# SCH_card1_2024-03-21.net
KiCad netlist of a schematic drawn in EasyEDA
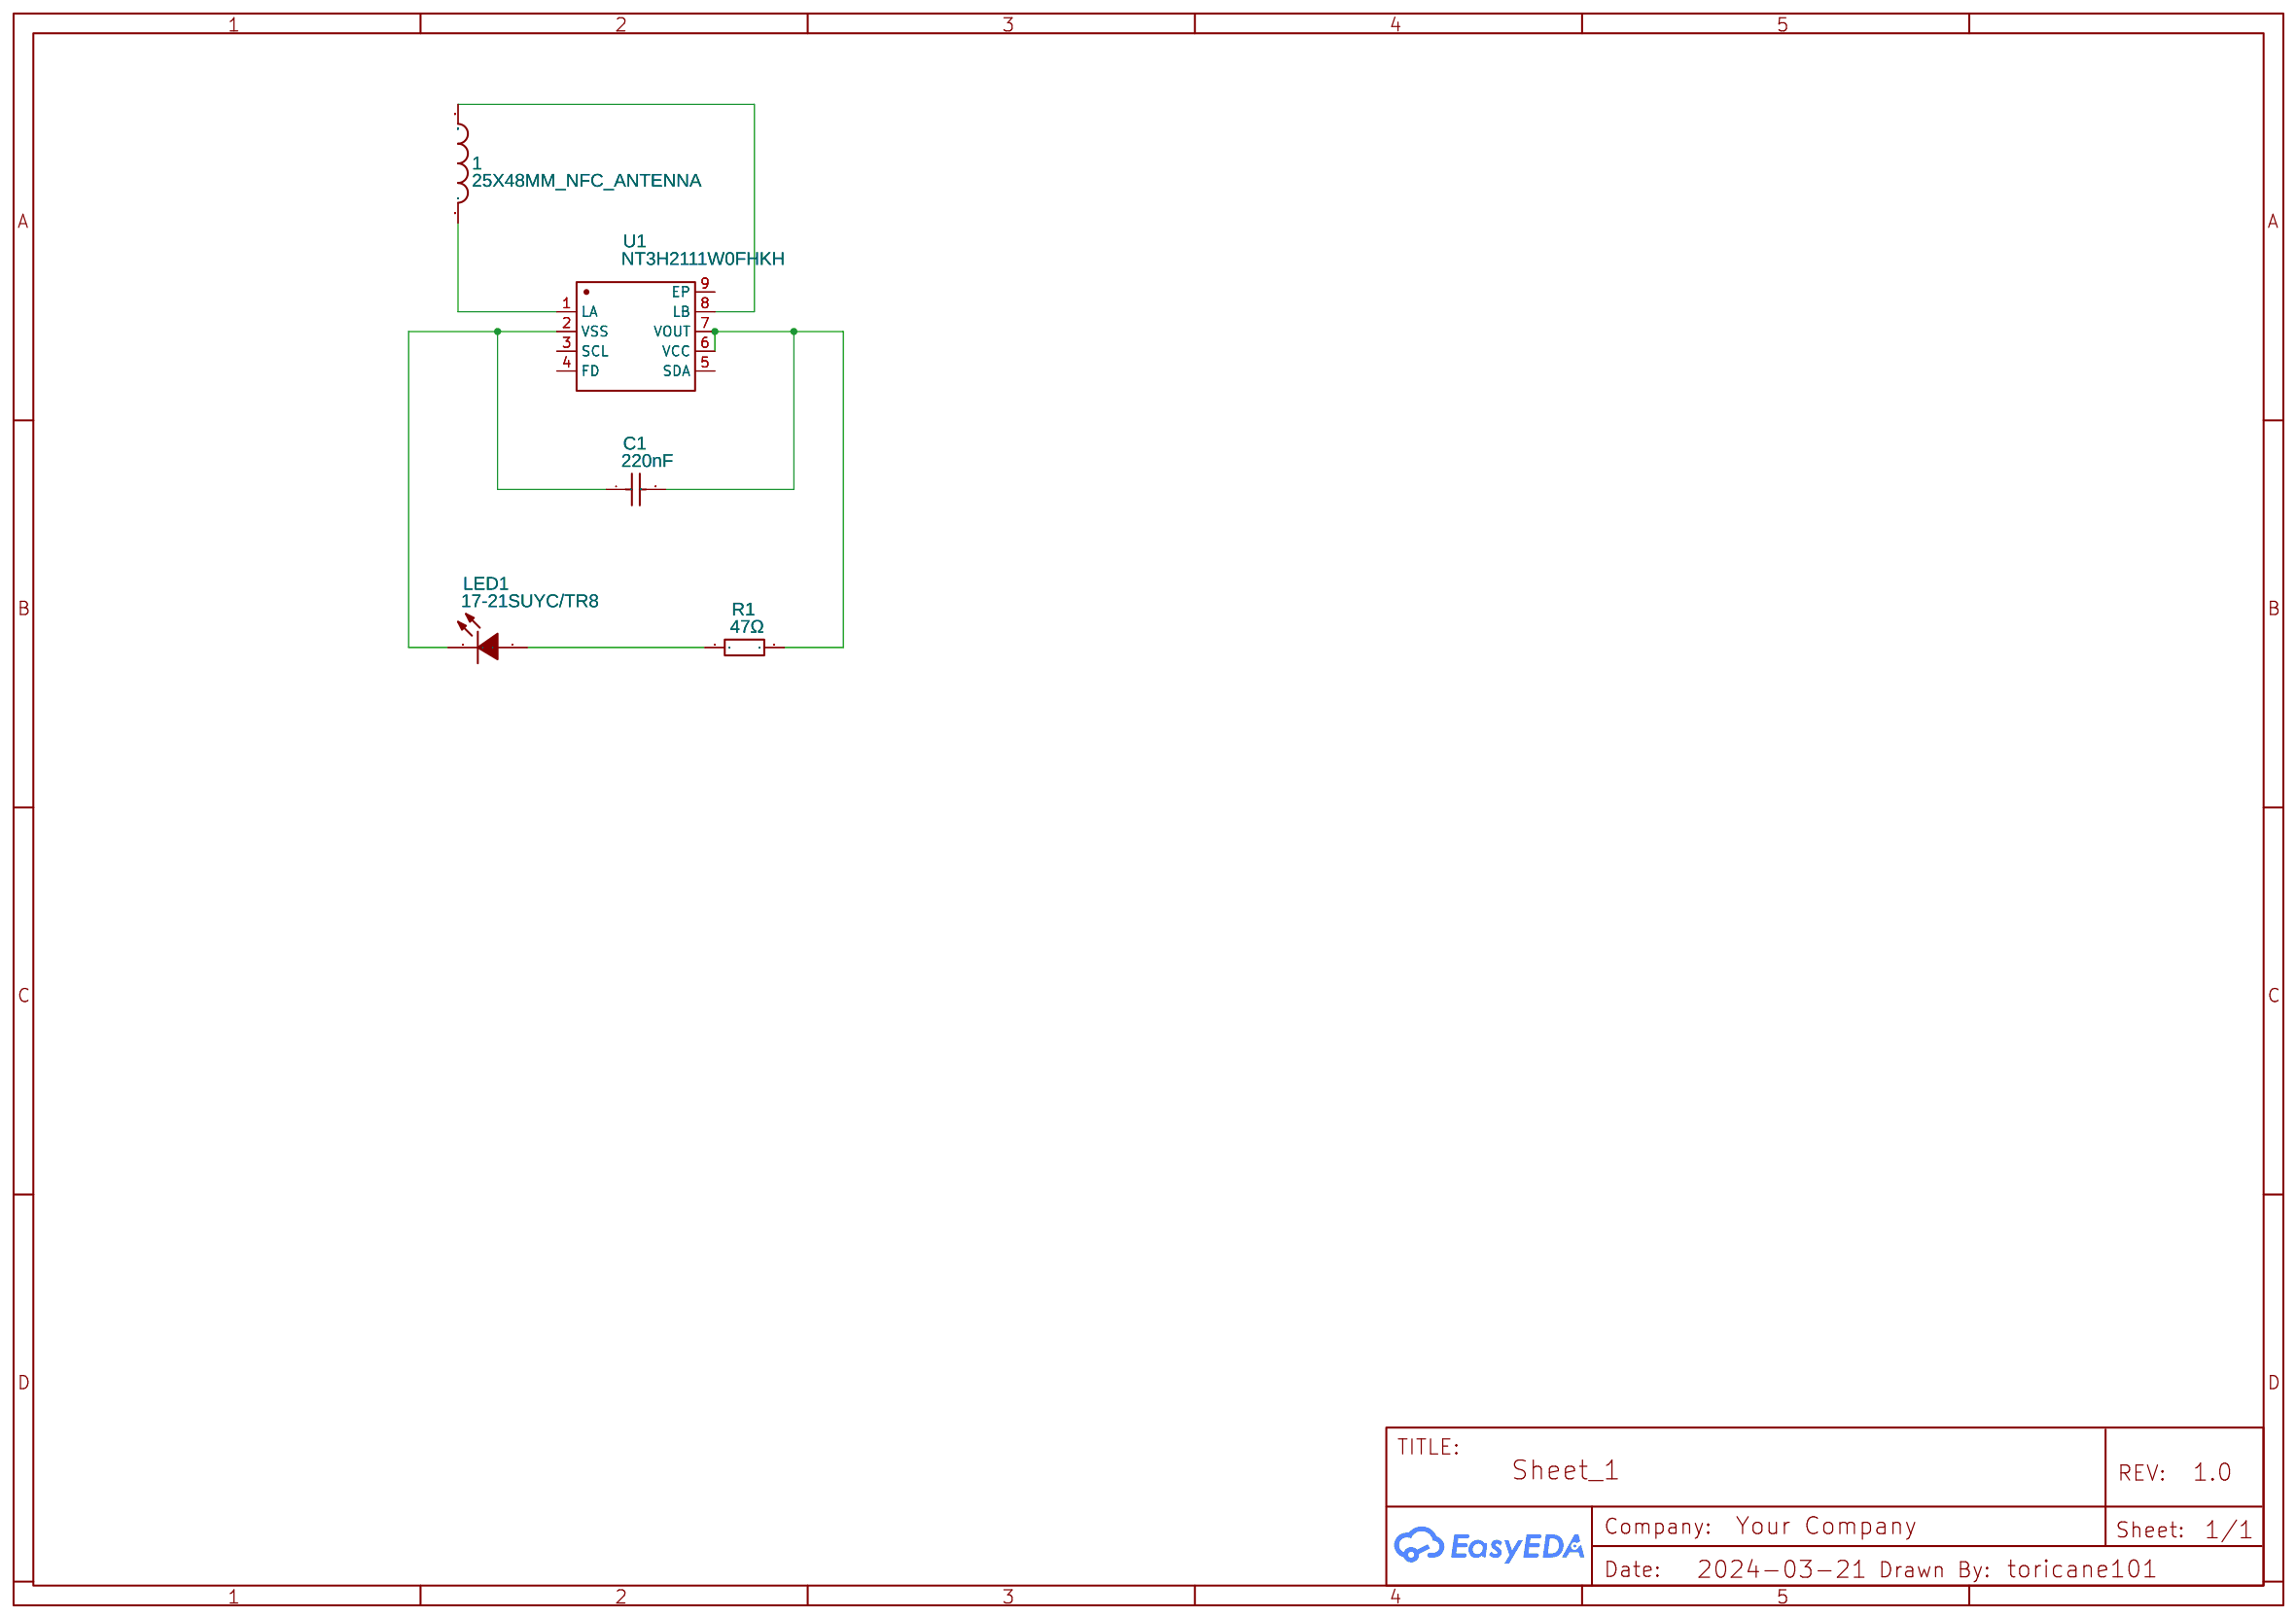
[diagram p0: schematic sheet]

(export (version "E")
  (design (tool "Eeschema 10.0.6"))
  (components
    (comp (ref "1") (value "25X48MM_NFC_ANTENNA") (libsource (lib "") (part "25X48MM_NFC_ANTENNA")))
    (comp (ref "C1")
      (value "220nF")
      (fields
        (field (name "Manufacturer Part") "CL10B224KA8NNNC")
        (field (name "Manufacturer") "SAMSUNG(三星)")
      )
      (libsource (lib "") (part "CL10B224KA8NNNC"))
    )
    (comp (ref "LED1")
      (value "17-21SUYC/TR8")
      (fields (field (name "Manufacturer Part") "KT-0805黄灯") (field (name "Manufacturer") "KENTO"))
      (libsource (lib "") (part "17-21SUYC/TR8"))
    )
    (comp (ref "R1")
      (value "47Ω")
      (fields
        (field (name "Manufacturer Part") "0603WAF470JT5E")
        (field (name "Manufacturer") "UNI-ROYAL(厚声)")
      )
      (libsource (lib "") (part "0603WAF470JT5E"))
    )
    (comp (ref "U1")
      (value "NT3H2111W0FHKH")
      (fields (field (name "Manufacturer") "NXP(恩智浦)"))
      (libsource (lib "") (part "NT3H2111W0FHKH"))
    )
  )
  (nets
    (net (code "1") (name "Net-(LED1-+)") (class "Default")
      (node (ref "LED1") (pin "1") (pinfunction "+_1") (pintype "unspecified"))
      (node (ref "R1") (pin "1") (pinfunction "1_1") (pintype "input"))
    )
    (net (code "2") (name "Net-(LED1--)") (class "Default")
      (node (ref "C1") (pin "1") (pinfunction "1_1") (pintype "input"))
      (node (ref "LED1") (pin "2") (pinfunction "-_2") (pintype "unspecified"))
      (node (ref "U1") (pin "2") (pinfunction "VSS_2") (pintype "unspecified"))
    )
    (net (code "3") (name "Net-(U1-LA)") (class "Default")
      (node (ref "1") (pin "P$2") (pinfunction "P$2_P$2") (pintype "bidirectional"))
      (node (ref "U1") (pin "1") (pinfunction "LA_1") (pintype "unspecified"))
    )
    (net (code "4") (name "Net-(U1-LB)") (class "Default")
      (node (ref "1") (pin "P$1") (pinfunction "P$1_P$1") (pintype "bidirectional"))
      (node (ref "U1") (pin "8") (pinfunction "LB_8") (pintype "unspecified"))
    )
    (net (code "5") (name "Net-(U1-VCC)") (class "Default")
      (node (ref "C1") (pin "2") (pinfunction "2_2") (pintype "input"))
      (node (ref "R1") (pin "2") (pinfunction "2_2") (pintype "input"))
      (node (ref "U1") (pin "6") (pinfunction "VCC_6") (pintype "unspecified"))
      (node (ref "U1") (pin "7") (pinfunction "VOUT_7") (pintype "unspecified"))
    )
    (net (code "6") (name "unconnected-(U1-EP-Pad9)") (class "Default")
      (node (ref "U1") (pin "9") (pinfunction "EP_9") (pintype "unspecified"))
    )
    (net (code "7") (name "unconnected-(U1-FD-Pad4)") (class "Default")
      (node (ref "U1") (pin "4") (pinfunction "FD_4") (pintype "unspecified"))
    )
    (net (code "8") (name "unconnected-(U1-SCL-Pad3)") (class "Default")
      (node (ref "U1") (pin "3") (pinfunction "SCL_3") (pintype "unspecified"))
    )
    (net (code "9") (name "unconnected-(U1-SDA-Pad5)") (class "Default")
      (node (ref "U1") (pin "5") (pinfunction "SDA_5") (pintype "unspecified"))
    )
  )
)
